# mimuz-ch55x.net
KiCad netlist of a schematic drawn in EAGLE
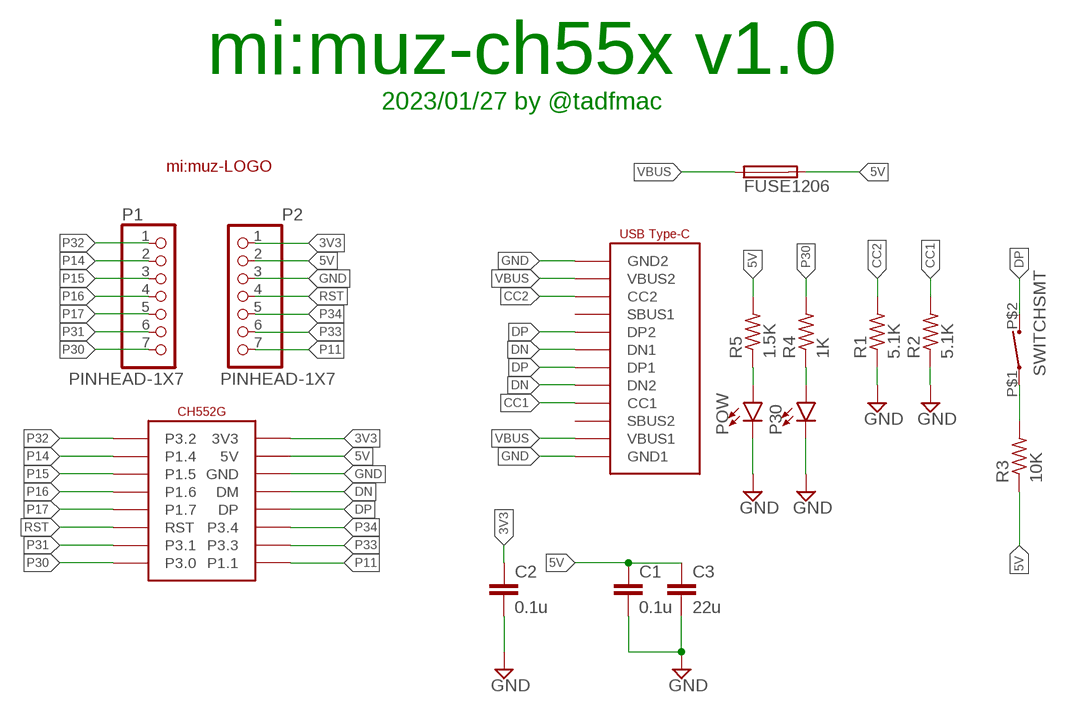
[diagram p0: schematic, sheet 1]

(export (version "E")
  (design (tool "Eeschema 10.0.6"))
  (components
    (comp (ref "*")
      (value "CH552G")
      (footprint "eagle-import:SOIC16")
      (libsource (lib "eagle-import") (part "CH552G"))
    )
    (comp (ref "C1")
      (value "0.1u")
      (footprint "eagle-import:C0603")
      (libsource (lib "eagle-import") (part "C-EUC0603"))
    )
    (comp (ref "C2")
      (value "0.1u")
      (footprint "eagle-import:C0603")
      (libsource (lib "eagle-import") (part "C-EUC0603"))
    )
    (comp (ref "C3")
      (value "22u")
      (footprint "eagle-import:C0805")
      (libsource (lib "eagle-import") (part "C-EUC0805"))
    )
    (comp (ref "P1")
      (value "PINHEAD-1X7")
      (footprint "eagle-import:PINHEAD-1X7")
      (libsource (lib "eagle-import") (part "PINHEAD-1X7"))
    )
    (comp (ref "P2")
      (value "PINHEAD-1X7")
      (footprint "eagle-import:PINHEAD-1X7")
      (libsource (lib "eagle-import") (part "PINHEAD-1X7"))
    )
    (comp (ref "P30")
      (value "LED")
      (footprint "eagle-import:LED-0603")
      (libsource (lib "eagle-import") (part "LED"))
    )
    (comp (ref "POW")
      (value "LED")
      (footprint "eagle-import:LED-0603")
      (libsource (lib "eagle-import") (part "LED"))
    )
    (comp (ref "R1")
      (value "5.1K")
      (footprint "eagle-import:R0603")
      (libsource (lib "eagle-import") (part "R-US_R0603"))
    )
    (comp (ref "R2")
      (value "5.1K")
      (footprint "eagle-import:R0603")
      (libsource (lib "eagle-import") (part "R-US_R0603"))
    )
    (comp (ref "R3")
      (value "10K")
      (footprint "eagle-import:R0603")
      (libsource (lib "eagle-import") (part "R-US_R0603"))
    )
    (comp (ref "R4")
      (value "1K")
      (footprint "eagle-import:R0603")
      (libsource (lib "eagle-import") (part "R-US_R0603"))
    )
    (comp (ref "R5")
      (value "1.5K")
      (footprint "eagle-import:R0603")
      (libsource (lib "eagle-import") (part "R-US_R0603"))
    )
    (comp (ref "U$1")
      (value "MIMUZ6MM")
      (footprint "eagle-import:MIMUZ-SMALL")
      (libsource (lib "eagle-import") (part "MIMUZ6MM"))
    )
    (comp (ref "U$2")
      (value "USB-C")
      (footprint "eagle-import:USB-C")
      (libsource (lib "eagle-import") (part "USB-C"))
    )
    (comp (ref "U$3")
      (value "FUSE1206")
      (footprint "eagle-import:F1206")
      (libsource (lib "eagle-import") (part "FUSE1206"))
    )
    (comp (ref "U$4")
      (value "SWITCHSMT")
      (footprint "eagle-import:SWITCH-SMT-2_4_3")
      (libsource (lib "eagle-import") (part "SWITCHSMT"))
    )
  )
  (nets
    (net (code "1") (name "3V3") (class "Default")
      (node (ref "*") (pin "16") (pinfunction "3V3_16") (pintype "bidirectional"))
      (node (ref "C2") (pin "1") (pinfunction "1_1") (pintype "passive"))
      (node (ref "P2") (pin "1") (pinfunction "1_1") (pintype "passive"))
    )
    (net (code "2") (name "5V") (class "Default")
      (node (ref "*") (pin "15") (pinfunction "5V_15") (pintype "bidirectional"))
      (node (ref "C1") (pin "1") (pinfunction "1_1") (pintype "passive"))
      (node (ref "C3") (pin "1") (pinfunction "1_1") (pintype "passive"))
      (node (ref "P2") (pin "2") (pinfunction "2_2") (pintype "passive"))
      (node (ref "R3") (pin "1") (pinfunction "1_1") (pintype "passive"))
      (node (ref "R5") (pin "2") (pinfunction "2_2") (pintype "passive"))
      (node (ref "U$3") (pin "2") (pinfunction "2_2") (pintype "passive"))
    )
    (net (code "3") (name "CC1") (class "Default")
      (node (ref "R2") (pin "2") (pinfunction "2_2") (pintype "passive"))
      (node (ref "U$2") (pin "CC1") (pinfunction "CC1_CC1") (pintype "bidirectional"))
    )
    (net (code "4") (name "CC2") (class "Default")
      (node (ref "R1") (pin "2") (pinfunction "2_2") (pintype "passive"))
      (node (ref "U$2") (pin "CC2") (pinfunction "CC2_CC2") (pintype "bidirectional"))
    )
    (net (code "5") (name "DN") (class "Default")
      (node (ref "*") (pin "13") (pinfunction "DM_13") (pintype "bidirectional"))
      (node (ref "U$2") (pin "DN1") (pinfunction "DN1_DN1") (pintype "bidirectional"))
      (node (ref "U$2") (pin "DN2") (pinfunction "DN2_DN2") (pintype "bidirectional"))
    )
    (net (code "6") (name "DP") (class "Default")
      (node (ref "*") (pin "12") (pinfunction "DP_12") (pintype "bidirectional"))
      (node (ref "U$2") (pin "DP1") (pinfunction "DP1_DP1") (pintype "bidirectional"))
      (node (ref "U$2") (pin "DP2") (pinfunction "DP2_DP2") (pintype "bidirectional"))
      (node (ref "U$4") (pin "P$2") (pinfunction "2_P$2") (pintype "passive"))
    )
    (net (code "7") (name "GND") (class "Default")
      (node (ref "*") (pin "14") (pinfunction "GND_14") (pintype "bidirectional"))
      (node (ref "C1") (pin "2") (pinfunction "2_2") (pintype "passive"))
      (node (ref "C2") (pin "2") (pinfunction "2_2") (pintype "passive"))
      (node (ref "C3") (pin "2") (pinfunction "2_2") (pintype "passive"))
      (node (ref "P2") (pin "3") (pinfunction "3_3") (pintype "passive"))
      (node (ref "P30") (pin "C") (pinfunction "C_C") (pintype "passive"))
      (node (ref "POW") (pin "C") (pinfunction "C_C") (pintype "passive"))
      (node (ref "R1") (pin "1") (pinfunction "1_1") (pintype "passive"))
      (node (ref "R2") (pin "1") (pinfunction "1_1") (pintype "passive"))
      (node (ref "U$2") (pin "GND1") (pinfunction "GND1_GND1") (pintype "bidirectional"))
      (node (ref "U$2") (pin "GND2") (pinfunction "GND2_GND2") (pintype "bidirectional"))
    )
    (net (code "8") (name "Net-(P30-PadA)") (class "Default")
      (node (ref "P30") (pin "A") (pinfunction "A_A") (pintype "passive"))
      (node (ref "R4") (pin "1") (pinfunction "1_1") (pintype "passive"))
    )
    (net (code "9") (name "Net-(POW-PadA)") (class "Default")
      (node (ref "POW") (pin "A") (pinfunction "A_A") (pintype "passive"))
      (node (ref "R5") (pin "1") (pinfunction "1_1") (pintype "passive"))
    )
    (net (code "10") (name "Net-(U$4-1)") (class "Default")
      (node (ref "R3") (pin "2") (pinfunction "2_2") (pintype "passive"))
      (node (ref "U$4") (pin "P$1") (pinfunction "1_P$1") (pintype "passive"))
    )
    (net (code "11") (name "P11") (class "Default")
      (node (ref "*") (pin "9") (pinfunction "P1.1_9") (pintype "bidirectional"))
      (node (ref "P2") (pin "7") (pinfunction "7_7") (pintype "passive"))
    )
    (net (code "12") (name "P14") (class "Default")
      (node (ref "*") (pin "2") (pinfunction "P1.4_2") (pintype "bidirectional"))
      (node (ref "P1") (pin "2") (pinfunction "2_2") (pintype "passive"))
    )
    (net (code "13") (name "P15") (class "Default")
      (node (ref "*") (pin "3") (pinfunction "P1.5_3") (pintype "bidirectional"))
      (node (ref "P1") (pin "3") (pinfunction "3_3") (pintype "passive"))
    )
    (net (code "14") (name "P16") (class "Default")
      (node (ref "*") (pin "4") (pinfunction "P1.6_4") (pintype "bidirectional"))
      (node (ref "P1") (pin "4") (pinfunction "4_4") (pintype "passive"))
    )
    (net (code "15") (name "P17") (class "Default")
      (node (ref "*") (pin "5") (pinfunction "P1.7_5") (pintype "bidirectional"))
      (node (ref "P1") (pin "5") (pinfunction "5_5") (pintype "passive"))
    )
    (net (code "16") (name "P30") (class "Default")
      (node (ref "*") (pin "8") (pinfunction "P3.0_8") (pintype "bidirectional"))
      (node (ref "P1") (pin "7") (pinfunction "7_7") (pintype "passive"))
      (node (ref "R4") (pin "2") (pinfunction "2_2") (pintype "passive"))
    )
    (net (code "17") (name "P31") (class "Default")
      (node (ref "*") (pin "7") (pinfunction "P3.1_7") (pintype "bidirectional"))
      (node (ref "P1") (pin "6") (pinfunction "6_6") (pintype "passive"))
    )
    (net (code "18") (name "P32") (class "Default")
      (node (ref "*") (pin "1") (pinfunction "P3.2_1") (pintype "bidirectional"))
      (node (ref "P1") (pin "1") (pinfunction "1_1") (pintype "passive"))
    )
    (net (code "19") (name "P33") (class "Default")
      (node (ref "*") (pin "10") (pinfunction "P3.3_10") (pintype "bidirectional"))
      (node (ref "P2") (pin "6") (pinfunction "6_6") (pintype "passive"))
    )
    (net (code "20") (name "P34") (class "Default")
      (node (ref "*") (pin "11") (pinfunction "P3.4_11") (pintype "bidirectional"))
      (node (ref "P2") (pin "5") (pinfunction "5_5") (pintype "passive"))
    )
    (net (code "21") (name "RST") (class "Default")
      (node (ref "*") (pin "6") (pinfunction "RST_6") (pintype "bidirectional"))
      (node (ref "P2") (pin "4") (pinfunction "4_4") (pintype "passive"))
    )
    (net (code "22") (name "VBUS") (class "Default")
      (node (ref "U$2") (pin "VBUS1") (pinfunction "VBUS1_VBUS1") (pintype "bidirectional"))
      (node (ref "U$2") (pin "VBUS2") (pinfunction "VBUS2_VBUS2") (pintype "bidirectional"))
      (node (ref "U$3") (pin "1") (pinfunction "1_1") (pintype "passive"))
    )
    (net (code "23") (name "unconnected-(U$2-PadSBUS1)") (class "Default")
      (node (ref "U$2") (pin "SBUS1") (pinfunction "SBUS1_SBUS1") (pintype "bidirectional"))
    )
    (net (code "24") (name "unconnected-(U$2-PadSBUS2)") (class "Default")
      (node (ref "U$2") (pin "SBUS2") (pinfunction "SBUS2_SBUS2") (pintype "bidirectional"))
    )
  )
)
